# Motor_Controller_V_5_1.net
KiCad netlist of a schematic drawn in EAGLE
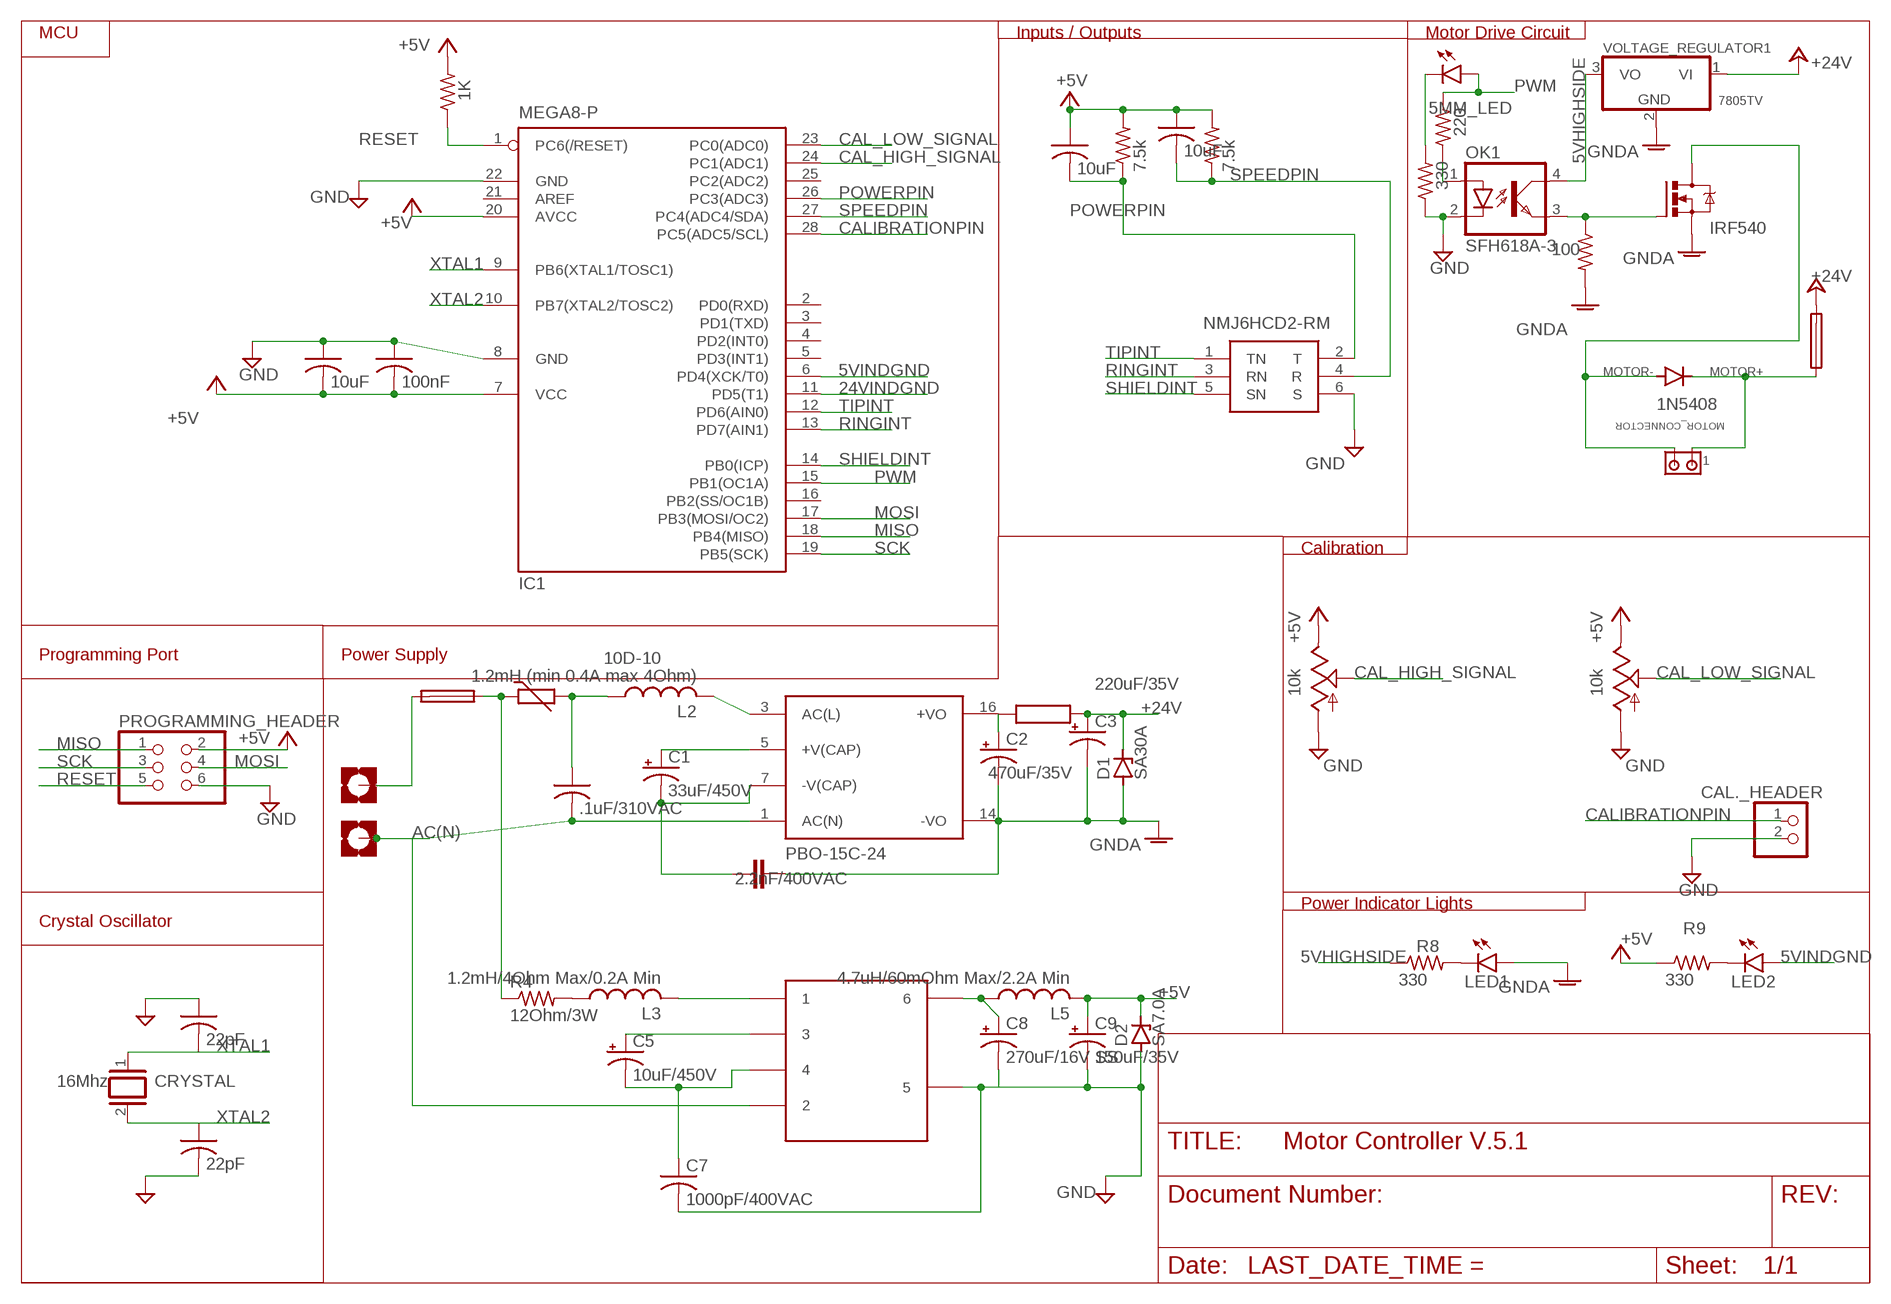
[diagram p0: schematic, sheet 1]

(export (version "E")
  (design (tool "Eeschema 10.0.6"))
  (components
    (comp (ref "1N5408")
      (value "1N5408")
      (footprint "eagle-import:DO201-15")
      (fields (field (name "MF") "VISHAY") (field (name "MPN") "1N5408-E3/54"))
      (libsource (lib "eagle-import") (part "1N5400"))
    )
    (comp (ref "AC(N)")
      (value "PAD3.0")
      (footprint "eagle-import:3,0-PAD-SQUARE")
      (libsource (lib "eagle-import") (part "PAD3.0"))
    )
    (comp (ref "C1")
      (value "33uF/450V")
      (footprint "eagle-import:E5-13")
      (libsource (lib "eagle-import") (part "CPOL-USE5-13"))
    )
    (comp (ref "C2")
      (value "470uF/35V")
      (footprint "eagle-import:E5-10,5")
      (fields (field (name "MF") "PANASONIC") (field (name "MPN") "ECA1VHG471B"))
      (libsource (lib "eagle-import") (part "CPOL-USE5-10.5"))
    )
    (comp (ref "C3")
      (value "220uF/35V")
      (footprint "eagle-import:E5-10,5")
      (fields (field (name "MF") "KEMET") (field (name "MPN") "A768KS227M1VLAE024"))
      (libsource (lib "eagle-import") (part "CPOL-USE5-10.5"))
    )
    (comp (ref "C4")
      (value ".1uF/310VAC")
      (footprint "eagle-import:C102-064X133")
      (libsource (lib "eagle-import") (part "CMPP_AC275V104K10S6"))
    )
    (comp (ref "C5")
      (value "10uF/450V")
      (footprint "eagle-import:E5-10,5")
      (libsource (lib "eagle-import") (part "CPOL-USE5-10.5"))
    )
    (comp (ref "C6")
      (value "22pF")
      (footprint "eagle-import:C025-024X044")
      (libsource (lib "eagle-import") (part "C-US025-024X044"))
    )
    (comp (ref "C7")
      (value "1000pF/400VAC")
      (footprint "eagle-import:C075-052X106")
      (libsource (lib "eagle-import") (part "C-US075-052X106"))
    )
    (comp (ref "C8")
      (value "270uF/16V SS")
      (footprint "eagle-import:E2,5-6")
      (libsource (lib "eagle-import") (part "CPOL-USE2.5-6"))
    )
    (comp (ref "C9")
      (value "150uF/35V")
      (footprint "eagle-import:E3,5-8")
      (libsource (lib "eagle-import") (part "CPOL-USE3.5-8"))
    )
    (comp (ref "C10")
      (value "10uF")
      (footprint "eagle-import:C025-024X044")
      (libsource (lib "eagle-import") (part "C-US025-024X044"))
    )
    (comp (ref "C12")
      (value "10uF")
      (footprint "eagle-import:C025-024X044")
      (libsource (lib "eagle-import") (part "C-US025-024X044"))
    )
    (comp (ref "C13")
      (value "10uF")
      (footprint "eagle-import:C025-024X044")
      (libsource (lib "eagle-import") (part "C-US025-024X044"))
    )
    (comp (ref "C14")
      (value "100nF")
      (footprint "eagle-import:C025-024X044")
      (libsource (lib "eagle-import") (part "C-US025-024X044"))
    )
    (comp (ref "C15")
      (value "22pF")
      (footprint "eagle-import:C025-024X044")
      (libsource (lib "eagle-import") (part "C-US025-024X044"))
    )
    (comp (ref "CAL._HEADER")
      (value "PINHD-1X2")
      (footprint "eagle-import:1X02")
      (libsource (lib "eagle-import") (part "PINHD-1X2"))
    )
    (comp (ref "CRYSTAL")
      (value "16Mhz")
      (footprint "eagle-import:QS")
      (libsource (lib "eagle-import") (part "XTAL/S"))
    )
    (comp (ref "CY1")
      (value "2.2nF/400VAC")
      (footprint "eagle-import:YC10B4")
      (libsource (lib "eagle-import") (part "CYYC10B4"))
    )
    (comp (ref "D1")
      (value "SA30A")
      (footprint "eagle-import:TVS-10")
      (libsource (lib "eagle-import") (part "TVSDIO"))
    )
    (comp (ref "D2")
      (value "SA7.0A")
      (footprint "eagle-import:TVS-10")
      (libsource (lib "eagle-import") (part "TVSDIO"))
    )
    (comp (ref "F1")
      (value "FUSESH22,5")
      (footprint "eagle-import:SH22,5")
      (libsource (lib "eagle-import") (part "FUSESH22,5"))
    )
    (comp (ref "F2")
      (value "1A/300V")
      (footprint "eagle-import:SH22,5")
      (libsource (lib "eagle-import") (part "FUSESH22,5"))
    )
    (comp (ref "FAST")
      (value "10k")
      (footprint "eagle-import:CT6")
      (libsource (lib "eagle-import") (part "TRIM_US-CT6"))
    )
    (comp (ref "H1")
      (value "PAD3.0")
      (footprint "eagle-import:3,0-PAD-SQUARE")
      (libsource (lib "eagle-import") (part "PAD3.0"))
    )
    (comp (ref "IC1")
      (value "MEGA8-P")
      (footprint "eagle-import:DIL28-3")
      (libsource (lib "eagle-import") (part "MEGA8-P"))
    )
    (comp (ref "J1")
      (value "NMJ6HCD2-RM")
      (footprint "eagle-import:NMJ6HCD2RM")
      (fields (field (name "MOUSER_PART_NUMBER") "568-NMJ6HCD2-RM"))
      (libsource (lib "eagle-import") (part "NMJ6HCD2-RM"))
    )
    (comp (ref "L2")
      (value "1.2mH (min 0.4A max 4Ohm)")
      (footprint "eagle-import:RCP1317_INDUCTOR")
      (libsource (lib "eagle-import") (part "RCP_1317_INDUCTOR"))
    )
    (comp (ref "L3")
      (value "1.2mH/4Ohm Max/0.2A Min")
      (footprint "eagle-import:RCP1317_INDUCTOR")
      (libsource (lib "eagle-import") (part "RCP_1317_INDUCTOR"))
    )
    (comp (ref "L5")
      (value "4.7uH/60mOhm Max/2.2A Min")
      (footprint "eagle-import:RLB0914_INDUCTOR")
      (libsource (lib "eagle-import") (part "RLB0914_INDUCTOR"))
    )
    (comp (ref "LED1")
      (value "LED3MM")
      (footprint "eagle-import:LED3MM")
      (libsource (lib "eagle-import") (part "LED3MM"))
    )
    (comp (ref "LED2")
      (value "LED3MM")
      (footprint "eagle-import:LED3MM")
      (libsource (lib "eagle-import") (part "LED3MM"))
    )
    (comp (ref "MOTOR_CONNECTOR")
      (value "MATE-N-LOK_193839-1")
      (footprint "eagle-import:MATE-N-LOK_2PIN_CONNECTOR")
      (libsource (lib "eagle-import") (part "MATE-N-LOK_193839-1"))
    )
    (comp (ref "OK1")
      (value "SFH618A-3")
      (footprint "eagle-import:DIP4")
      (fields (field (name "MF") "VISHAY/TELEFUNKEN"))
      (libsource (lib "eagle-import") (part "SFH618?A-3"))
    )
    (comp (ref "PROGRAMMING_HEADER")
      (value "PINHD-2X3")
      (footprint "eagle-import:2X03")
      (libsource (lib "eagle-import") (part "PINHD-2X3"))
    )
    (comp (ref "PS1")
      (value "PBO-15C-24")
      (footprint "eagle-import:CONV_PBO-15C-24")
      (fields (field (name "MF") "CUI Inc."))
      (libsource (lib "eagle-import") (part "PBO-15C-24"))
    )
    (comp (ref "Q1")
      (value "IRF540")
      (footprint "eagle-import:TO220BV")
      (libsource (lib "eagle-import") (part "IRF540"))
    )
    (comp (ref "R1")
      (value "10D-10")
      (footprint "eagle-import:R-7,5")
      (libsource (lib "eagle-import") (part "THERMISTOR-7,5"))
    )
    (comp (ref "R2")
      (value "1K")
      (footprint "eagle-import:0204_7")
      (libsource (lib "eagle-import") (part "R-US_0204/7"))
    )
    (comp (ref "R3")
      (value "7.5k")
      (footprint "eagle-import:0204_7")
      (libsource (lib "eagle-import") (part "R-US_0204/7"))
    )
    (comp (ref "R4")
      (value "12Ohm/3W")
      (footprint "eagle-import:VTA52")
      (libsource (lib "eagle-import") (part "R-US_VTA52"))
    )
    (comp (ref "R5")
      (value "220")
      (footprint "eagle-import:0204_7")
      (libsource (lib "eagle-import") (part "R-US_0204/7"))
    )
    (comp (ref "R6")
      (value "100")
      (footprint "eagle-import:0204_7")
      (libsource (lib "eagle-import") (part "R-US_0204/7"))
    )
    (comp (ref "R7")
      (value "7.5k")
      (footprint "eagle-import:0204_7")
      (libsource (lib "eagle-import") (part "R-US_0204/7"))
    )
    (comp (ref "R8")
      (value "330")
      (footprint "eagle-import:0204_7")
      (libsource (lib "eagle-import") (part "R-US_0204/7"))
    )
    (comp (ref "R9")
      (value "330")
      (footprint "eagle-import:0204_7")
      (libsource (lib "eagle-import") (part "R-US_0204/7"))
    )
    (comp (ref "R10")
      (value "330")
      (footprint "eagle-import:0204_7")
      (libsource (lib "eagle-import") (part "R-US_0204/7"))
    )
    (comp (ref "SLOW")
      (value "10k")
      (footprint "eagle-import:CT6")
      (libsource (lib "eagle-import") (part "TRIM_US-CT6"))
    )
    (comp (ref "U$1")
      (value "L503-13B05R")
      (footprint "eagle-import:LS03-13BO5R3")
      (libsource (lib "eagle-import") (part "L503-13B05R"))
    )
    (comp (ref "U$2")
      (value "HCTI-22-16.4")
      (footprint "eagle-import:HCTI-22-16.4")
      (libsource (lib "eagle-import") (part "HCTI-22-16.4"))
    )
    (comp (ref "U$3")
      (value "5MM_LED")
      (footprint "eagle-import:5MM_LED")
      (libsource (lib "eagle-import") (part "5MM_LED"))
    )
    (comp (ref "VOLTAGE_REGULATOR1")
      (value "7805TV")
      (footprint "eagle-import:TO220V")
      (libsource (lib "eagle-import") (part "78TV05"))
    )
  )
  (nets
    (net (code "1") (name "+5V") (class "Default")
      (node (ref "C10") (pin "1") (pinfunction "1_1") (pintype "passive"))
      (node (ref "C12") (pin "1") (pinfunction "1_1") (pintype "passive"))
      (node (ref "C13") (pin "2") (pinfunction "2_2") (pintype "passive"))
      (node (ref "C14") (pin "2") (pinfunction "2_2") (pintype "passive"))
      (node (ref "C9") (pin "+") (pinfunction "+_+") (pintype "passive"))
      (node (ref "D2") (pin "C") (pinfunction "C_C") (pintype "passive"))
      (node (ref "FAST") (pin "E") (pinfunction "E_E") (pintype "passive"))
      (node (ref "IC1") (pin "20") (pinfunction "AVCC_20") (pintype "power_in"))
      (node (ref "IC1") (pin "7") (pinfunction "VCC_7") (pintype "power_in"))
      (node (ref "L5") (pin "P$2") (pinfunction "2_P$2") (pintype "passive"))
      (node (ref "PROGRAMMING_HEADER") (pin "2") (pinfunction "2_2") (pintype "passive"))
      (node (ref "R2") (pin "2") (pinfunction "2_2") (pintype "passive"))
      (node (ref "R3") (pin "2") (pinfunction "2_2") (pintype "passive"))
      (node (ref "R7") (pin "2") (pinfunction "2_2") (pintype "passive"))
      (node (ref "R9") (pin "1") (pinfunction "1_1") (pintype "passive"))
      (node (ref "SLOW") (pin "E") (pinfunction "E_E") (pintype "passive"))
    )
    (net (code "2") (name "+24V") (class "Default")
      (node (ref "C3") (pin "+") (pinfunction "+_+") (pintype "passive"))
      (node (ref "D1") (pin "C") (pinfunction "C_C") (pintype "passive"))
      (node (ref "F1") (pin "2") (pinfunction "2_2") (pintype "passive"))
      (node (ref "U$2") (pin "P$2") (pinfunction "P$2_P$2") (pintype "bidirectional"))
      (node (ref "VOLTAGE_REGULATOR1") (pin "1") (pinfunction "VI_1") (pintype "input"))
    )
    (net (code "3") (name "/5VHIGHSIDE") (class "Default")
      (node (ref "OK1") (pin "4") (pinfunction "COL_4") (pintype "passive"))
      (node (ref "R8") (pin "1") (pinfunction "1_1") (pintype "passive"))
      (node (ref "VOLTAGE_REGULATOR1") (pin "3") (pinfunction "VO_3") (pintype "passive"))
    )
    (net (code "4") (name "/5VINDGND") (class "Default")
      (node (ref "IC1") (pin "6") (pinfunction "PD4(XCK/T0)_6") (pintype "bidirectional"))
      (node (ref "LED2") (pin "A") (pinfunction "A_A") (pintype "passive"))
    )
    (net (code "5") (name "/24VINDGND") (class "Default")
      (node (ref "IC1") (pin "11") (pinfunction "PD5(T1)_11") (pintype "bidirectional"))
    )
    (net (code "6") (name "/AC(N)") (class "Default")
      (node (ref "AC(N)") (pin "B3,0") (pinfunction "MOUNT_B3,0") (pintype "passive"))
      (node (ref "C4") (pin "2") (pinfunction "2_2") (pintype "passive"))
      (node (ref "PS1") (pin "1") (pinfunction "AC(N)_1") (pintype "input"))
      (node (ref "U$1") (pin "3") (pinfunction "2_3") (pintype "bidirectional"))
      (node (ref "U$1") (pin "4") (pinfunction "2_4") (pintype "bidirectional"))
    )
    (net (code "7") (name "/CALIBRATIONPIN") (class "Default")
      (node (ref "CAL._HEADER") (pin "1") (pinfunction "1_1") (pintype "passive"))
      (node (ref "IC1") (pin "28") (pinfunction "PC5(ADC5/SCL)_28") (pintype "bidirectional"))
    )
    (net (code "8") (name "/CAL_HIGH_SIGNAL") (class "Default")
      (node (ref "FAST") (pin "S") (pinfunction "S_S") (pintype "passive"))
      (node (ref "IC1") (pin "24") (pinfunction "PC1(ADC1)_24") (pintype "bidirectional"))
    )
    (net (code "9") (name "/CAL_LOW_SIGNAL") (class "Default")
      (node (ref "IC1") (pin "23") (pinfunction "PC0(ADC0)_23") (pintype "bidirectional"))
      (node (ref "SLOW") (pin "S") (pinfunction "S_S") (pintype "passive"))
    )
    (net (code "10") (name "/MISO") (class "Default")
      (node (ref "IC1") (pin "18") (pinfunction "PB4(MISO)_18") (pintype "bidirectional"))
      (node (ref "PROGRAMMING_HEADER") (pin "1") (pinfunction "1_1") (pintype "passive"))
    )
    (net (code "11") (name "/MOSI") (class "Default")
      (node (ref "IC1") (pin "17") (pinfunction "PB3(MOSI/OC2)_17") (pintype "bidirectional"))
      (node (ref "PROGRAMMING_HEADER") (pin "4") (pinfunction "4_4") (pintype "passive"))
    )
    (net (code "12") (name "/MOTOR+") (class "Default")
      (node (ref "1N5408") (pin "C") (pinfunction "C_C") (pintype "passive"))
      (node (ref "F1") (pin "1") (pinfunction "1_1") (pintype "passive"))
      (node (ref "MOTOR_CONNECTOR") (pin "P$1") (pinfunction "1_P$1") (pintype "passive"))
    )
    (net (code "13") (name "/MOTOR-") (class "Default")
      (node (ref "1N5408") (pin "A") (pinfunction "A_A") (pintype "passive"))
      (node (ref "MOTOR_CONNECTOR") (pin "P$2") (pinfunction "2_P$2") (pintype "passive"))
      (node (ref "Q1") (pin "D") (pinfunction "D_D") (pintype "passive"))
    )
    (net (code "14") (name "/POWERPIN") (class "Default")
      (node (ref "C10") (pin "2") (pinfunction "2_2") (pintype "passive"))
      (node (ref "IC1") (pin "26") (pinfunction "PC3(ADC3)_26") (pintype "bidirectional"))
      (node (ref "J1") (pin "2") (pinfunction "T_2") (pintype "bidirectional"))
      (node (ref "R3") (pin "1") (pinfunction "1_1") (pintype "passive"))
    )
    (net (code "15") (name "/PWM") (class "Default")
      (node (ref "IC1") (pin "15") (pinfunction "PB1(OC1A)_15") (pintype "bidirectional"))
      (node (ref "R5") (pin "2") (pinfunction "2_2") (pintype "passive"))
      (node (ref "U$3") (pin "A") (pinfunction "A_A") (pintype "passive"))
    )
    (net (code "16") (name "/RESET") (class "Default")
      (node (ref "IC1") (pin "1") (pinfunction "PC6(/RESET)_1") (pintype "bidirectional"))
      (node (ref "PROGRAMMING_HEADER") (pin "5") (pinfunction "5_5") (pintype "passive"))
      (node (ref "R2") (pin "1") (pinfunction "1_1") (pintype "passive"))
    )
    (net (code "17") (name "/RINGINT") (class "Default")
      (node (ref "IC1") (pin "13") (pinfunction "PD7(AIN1)_13") (pintype "bidirectional"))
      (node (ref "J1") (pin "3") (pinfunction "RN_3") (pintype "bidirectional"))
    )
    (net (code "18") (name "/SCK") (class "Default")
      (node (ref "IC1") (pin "19") (pinfunction "PB5(SCK)_19") (pintype "bidirectional"))
      (node (ref "PROGRAMMING_HEADER") (pin "3") (pinfunction "3_3") (pintype "passive"))
    )
    (net (code "19") (name "/SHIELDINT") (class "Default")
      (node (ref "IC1") (pin "14") (pinfunction "PB0(ICP)_14") (pintype "bidirectional"))
      (node (ref "J1") (pin "5") (pinfunction "SN_5") (pintype "bidirectional"))
    )
    (net (code "20") (name "/SPEEDPIN") (class "Default")
      (node (ref "C12") (pin "2") (pinfunction "2_2") (pintype "passive"))
      (node (ref "IC1") (pin "27") (pinfunction "PC4(ADC4/SDA)_27") (pintype "bidirectional"))
      (node (ref "J1") (pin "4") (pinfunction "R_4") (pintype "bidirectional"))
      (node (ref "R7") (pin "1") (pinfunction "1_1") (pintype "passive"))
    )
    (net (code "21") (name "/TIPINT") (class "Default")
      (node (ref "IC1") (pin "12") (pinfunction "PD6(AIN0)_12") (pintype "bidirectional"))
      (node (ref "J1") (pin "1") (pinfunction "TN_1") (pintype "bidirectional"))
    )
    (net (code "22") (name "/XTAL1") (class "Default")
      (node (ref "C15") (pin "2") (pinfunction "2_2") (pintype "passive"))
      (node (ref "CRYSTAL") (pin "1") (pinfunction "1_1") (pintype "passive"))
      (node (ref "IC1") (pin "9") (pinfunction "PB6(XTAL1/TOSC1)_9") (pintype "bidirectional"))
    )
    (net (code "23") (name "/XTAL2") (class "Default")
      (node (ref "C6") (pin "1") (pinfunction "1_1") (pintype "passive"))
      (node (ref "CRYSTAL") (pin "2") (pinfunction "2_2") (pintype "passive"))
      (node (ref "IC1") (pin "10") (pinfunction "PB7(XTAL2/TOSC2)_10") (pintype "bidirectional"))
    )
    (net (code "24") (name "GND") (class "Default")
      (node (ref "C13") (pin "1") (pinfunction "1_1") (pintype "passive"))
      (node (ref "C14") (pin "1") (pinfunction "1_1") (pintype "passive"))
      (node (ref "C15") (pin "1") (pinfunction "1_1") (pintype "passive"))
      (node (ref "C6") (pin "2") (pinfunction "2_2") (pintype "passive"))
      (node (ref "C7") (pin "2") (pinfunction "2_2") (pintype "passive"))
      (node (ref "C8") (pin "-") (pinfunction "-_-") (pintype "passive"))
      (node (ref "C9") (pin "-") (pinfunction "-_-") (pintype "passive"))
      (node (ref "CAL._HEADER") (pin "2") (pinfunction "2_2") (pintype "passive"))
      (node (ref "D2") (pin "A") (pinfunction "A_A") (pintype "passive"))
      (node (ref "FAST") (pin "A") (pinfunction "A_A") (pintype "passive"))
      (node (ref "IC1") (pin "22") (pinfunction "GND_22") (pintype "power_in"))
      (node (ref "IC1") (pin "8") (pinfunction "GND_8") (pintype "power_in"))
      (node (ref "J1") (pin "6") (pinfunction "S_6") (pintype "bidirectional"))
      (node (ref "OK1") (pin "2") (pinfunction "C_2") (pintype "passive"))
      (node (ref "PROGRAMMING_HEADER") (pin "6") (pinfunction "6_6") (pintype "passive"))
      (node (ref "R10") (pin "1") (pinfunction "1_1") (pintype "passive"))
      (node (ref "SLOW") (pin "A") (pinfunction "A_A") (pintype "passive"))
      (node (ref "U$1") (pin "10") (pinfunction "5_10") (pintype "bidirectional"))
      (node (ref "U$1") (pin "9") (pinfunction "5_9") (pintype "bidirectional"))
    )
    (net (code "25") (name "GNDA") (class "Default")
      (node (ref "C2") (pin "-") (pinfunction "-_-") (pintype "passive"))
      (node (ref "C3") (pin "-") (pinfunction "-_-") (pintype "passive"))
      (node (ref "CY1") (pin "1") (pinfunction "1_1") (pintype "passive"))
      (node (ref "D1") (pin "A") (pinfunction "A_A") (pintype "passive"))
      (node (ref "LED1") (pin "A") (pinfunction "A_A") (pintype "passive"))
      (node (ref "PS1") (pin "14") (pinfunction "-VO_14") (pintype "output"))
      (node (ref "Q1") (pin "S") (pinfunction "S_S") (pintype "passive"))
      (node (ref "R6") (pin "2") (pinfunction "2_2") (pintype "passive"))
      (node (ref "VOLTAGE_REGULATOR1") (pin "2") (pinfunction "GND_2") (pintype "passive"))
    )
    (net (code "26") (name "Net-(C5-Pad+)") (class "Default")
      (node (ref "C5") (pin "+") (pinfunction "+_+") (pintype "passive"))
      (node (ref "U$1") (pin "5") (pinfunction "3_5") (pintype "bidirectional"))
      (node (ref "U$1") (pin "6") (pinfunction "3_6") (pintype "bidirectional"))
    )
    (net (code "27") (name "Net-(C5-Pad-)") (class "Default")
      (node (ref "C5") (pin "-") (pinfunction "-_-") (pintype "passive"))
      (node (ref "C7") (pin "1") (pinfunction "1_1") (pintype "passive"))
      (node (ref "U$1") (pin "7") (pinfunction "4_7") (pintype "bidirectional"))
      (node (ref "U$1") (pin "8") (pinfunction "4_8") (pintype "bidirectional"))
    )
    (net (code "28") (name "Net-(F2-Pad1)") (class "Default")
      (node (ref "F2") (pin "1") (pinfunction "1_1") (pintype "passive"))
      (node (ref "R1") (pin "1") (pinfunction "1_1") (pintype "passive"))
      (node (ref "R4") (pin "1") (pinfunction "1_1") (pintype "passive"))
    )
    (net (code "29") (name "Net-(H1-MOUNT)") (class "Default")
      (node (ref "F2") (pin "2") (pinfunction "2_2") (pintype "passive"))
      (node (ref "H1") (pin "B3,0") (pinfunction "MOUNT_B3,0") (pintype "passive"))
    )
    (net (code "30") (name "Net-(L2-1)") (class "Default")
      (node (ref "C4") (pin "1") (pinfunction "1_1") (pintype "passive"))
      (node (ref "L2") (pin "P$1") (pinfunction "1_P$1") (pintype "passive"))
      (node (ref "R1") (pin "2") (pinfunction "2_2") (pintype "passive"))
    )
    (net (code "31") (name "Net-(L2-2)") (class "Default")
      (node (ref "L2") (pin "P$2") (pinfunction "2_P$2") (pintype "passive"))
      (node (ref "PS1") (pin "3") (pinfunction "AC(L)_3") (pintype "input"))
    )
    (net (code "32") (name "Net-(L3-1)") (class "Default")
      (node (ref "L3") (pin "P$1") (pinfunction "1_P$1") (pintype "passive"))
      (node (ref "R4") (pin "2") (pinfunction "2_2") (pintype "passive"))
    )
    (net (code "33") (name "Net-(L3-2)") (class "Default")
      (node (ref "L3") (pin "P$2") (pinfunction "2_P$2") (pintype "passive"))
      (node (ref "U$1") (pin "1") (pinfunction "1_1") (pintype "bidirectional"))
      (node (ref "U$1") (pin "2") (pinfunction "1_2") (pintype "bidirectional"))
    )
    (net (code "34") (name "Net-(L5-1)") (class "Default")
      (node (ref "C8") (pin "+") (pinfunction "+_+") (pintype "passive"))
      (node (ref "L5") (pin "P$1") (pinfunction "1_P$1") (pintype "passive"))
      (node (ref "U$1") (pin "11") (pinfunction "6_11") (pintype "bidirectional"))
      (node (ref "U$1") (pin "12") (pinfunction "6_12") (pintype "bidirectional"))
    )
    (net (code "35") (name "Net-(LED1-C)") (class "Default")
      (node (ref "LED1") (pin "K") (pinfunction "C_K") (pintype "passive"))
      (node (ref "R8") (pin "2") (pinfunction "2_2") (pintype "passive"))
    )
    (net (code "36") (name "Net-(LED2-C)") (class "Default")
      (node (ref "LED2") (pin "K") (pinfunction "C_K") (pintype "passive"))
      (node (ref "R9") (pin "2") (pinfunction "2_2") (pintype "passive"))
    )
    (net (code "37") (name "Net-(OK1-A)") (class "Default")
      (node (ref "OK1") (pin "1") (pinfunction "A_1") (pintype "passive"))
      (node (ref "R5") (pin "1") (pinfunction "1_1") (pintype "passive"))
    )
    (net (code "38") (name "Net-(OK1-EMIT)") (class "Default")
      (node (ref "OK1") (pin "3") (pinfunction "EMIT_3") (pintype "passive"))
      (node (ref "Q1") (pin "G") (pinfunction "G_G") (pintype "passive"))
      (node (ref "R6") (pin "1") (pinfunction "1_1") (pintype "passive"))
    )
    (net (code "39") (name "Net-(PS1-+V(CAP))") (class "Default")
      (node (ref "C1") (pin "+") (pinfunction "+_+") (pintype "passive"))
      (node (ref "PS1") (pin "5") (pinfunction "+V(CAP)_5") (pintype "passive"))
    )
    (net (code "40") (name "Net-(PS1-+VO)") (class "Default")
      (node (ref "C2") (pin "+") (pinfunction "+_+") (pintype "passive"))
      (node (ref "PS1") (pin "16") (pinfunction "+VO_16") (pintype "output"))
      (node (ref "U$2") (pin "P$1") (pinfunction "P$1_P$1") (pintype "bidirectional"))
    )
    (net (code "41") (name "Net-(PS1--V(CAP))") (class "Default")
      (node (ref "C1") (pin "-") (pinfunction "-_-") (pintype "passive"))
      (node (ref "CY1") (pin "2") (pinfunction "2_2") (pintype "passive"))
      (node (ref "PS1") (pin "7") (pinfunction "-V(CAP)_7") (pintype "passive"))
    )
    (net (code "42") (name "Net-(R10-Pad2)") (class "Default")
      (node (ref "R10") (pin "2") (pinfunction "2_2") (pintype "passive"))
      (node (ref "U$3") (pin "C") (pinfunction "C_C") (pintype "passive"))
    )
    (net (code "43") (name "unconnected-(IC1-AREF-Pad21)") (class "Default")
      (node (ref "IC1") (pin "21") (pinfunction "AREF_21") (pintype "passive"))
    )
    (net (code "44") (name "unconnected-(IC1-PB2(SS{slash}OC1B)-Pad16)") (class "Default")
      (node (ref "IC1") (pin "16") (pinfunction "PB2(SS/OC1B)_16") (pintype "bidirectional"))
    )
    (net (code "45") (name "unconnected-(IC1-PC2(ADC2)-Pad25)") (class "Default")
      (node (ref "IC1") (pin "25") (pinfunction "PC2(ADC2)_25") (pintype "bidirectional"))
    )
    (net (code "46") (name "unconnected-(IC1-PD0(RXD)-Pad2)") (class "Default")
      (node (ref "IC1") (pin "2") (pinfunction "PD0(RXD)_2") (pintype "bidirectional"))
    )
    (net (code "47") (name "unconnected-(IC1-PD1(TXD)-Pad3)") (class "Default")
      (node (ref "IC1") (pin "3") (pinfunction "PD1(TXD)_3") (pintype "bidirectional"))
    )
    (net (code "48") (name "unconnected-(IC1-PD2(INT0)-Pad4)") (class "Default")
      (node (ref "IC1") (pin "4") (pinfunction "PD2(INT0)_4") (pintype "bidirectional"))
    )
    (net (code "49") (name "unconnected-(IC1-PD3(INT1)-Pad5)") (class "Default")
      (node (ref "IC1") (pin "5") (pinfunction "PD3(INT1)_5") (pintype "bidirectional"))
    )
  )
)
